# uv-dosimeter-guva-op-amp-mk-1_1.net
KiCad netlist of a schematic drawn in EAGLE
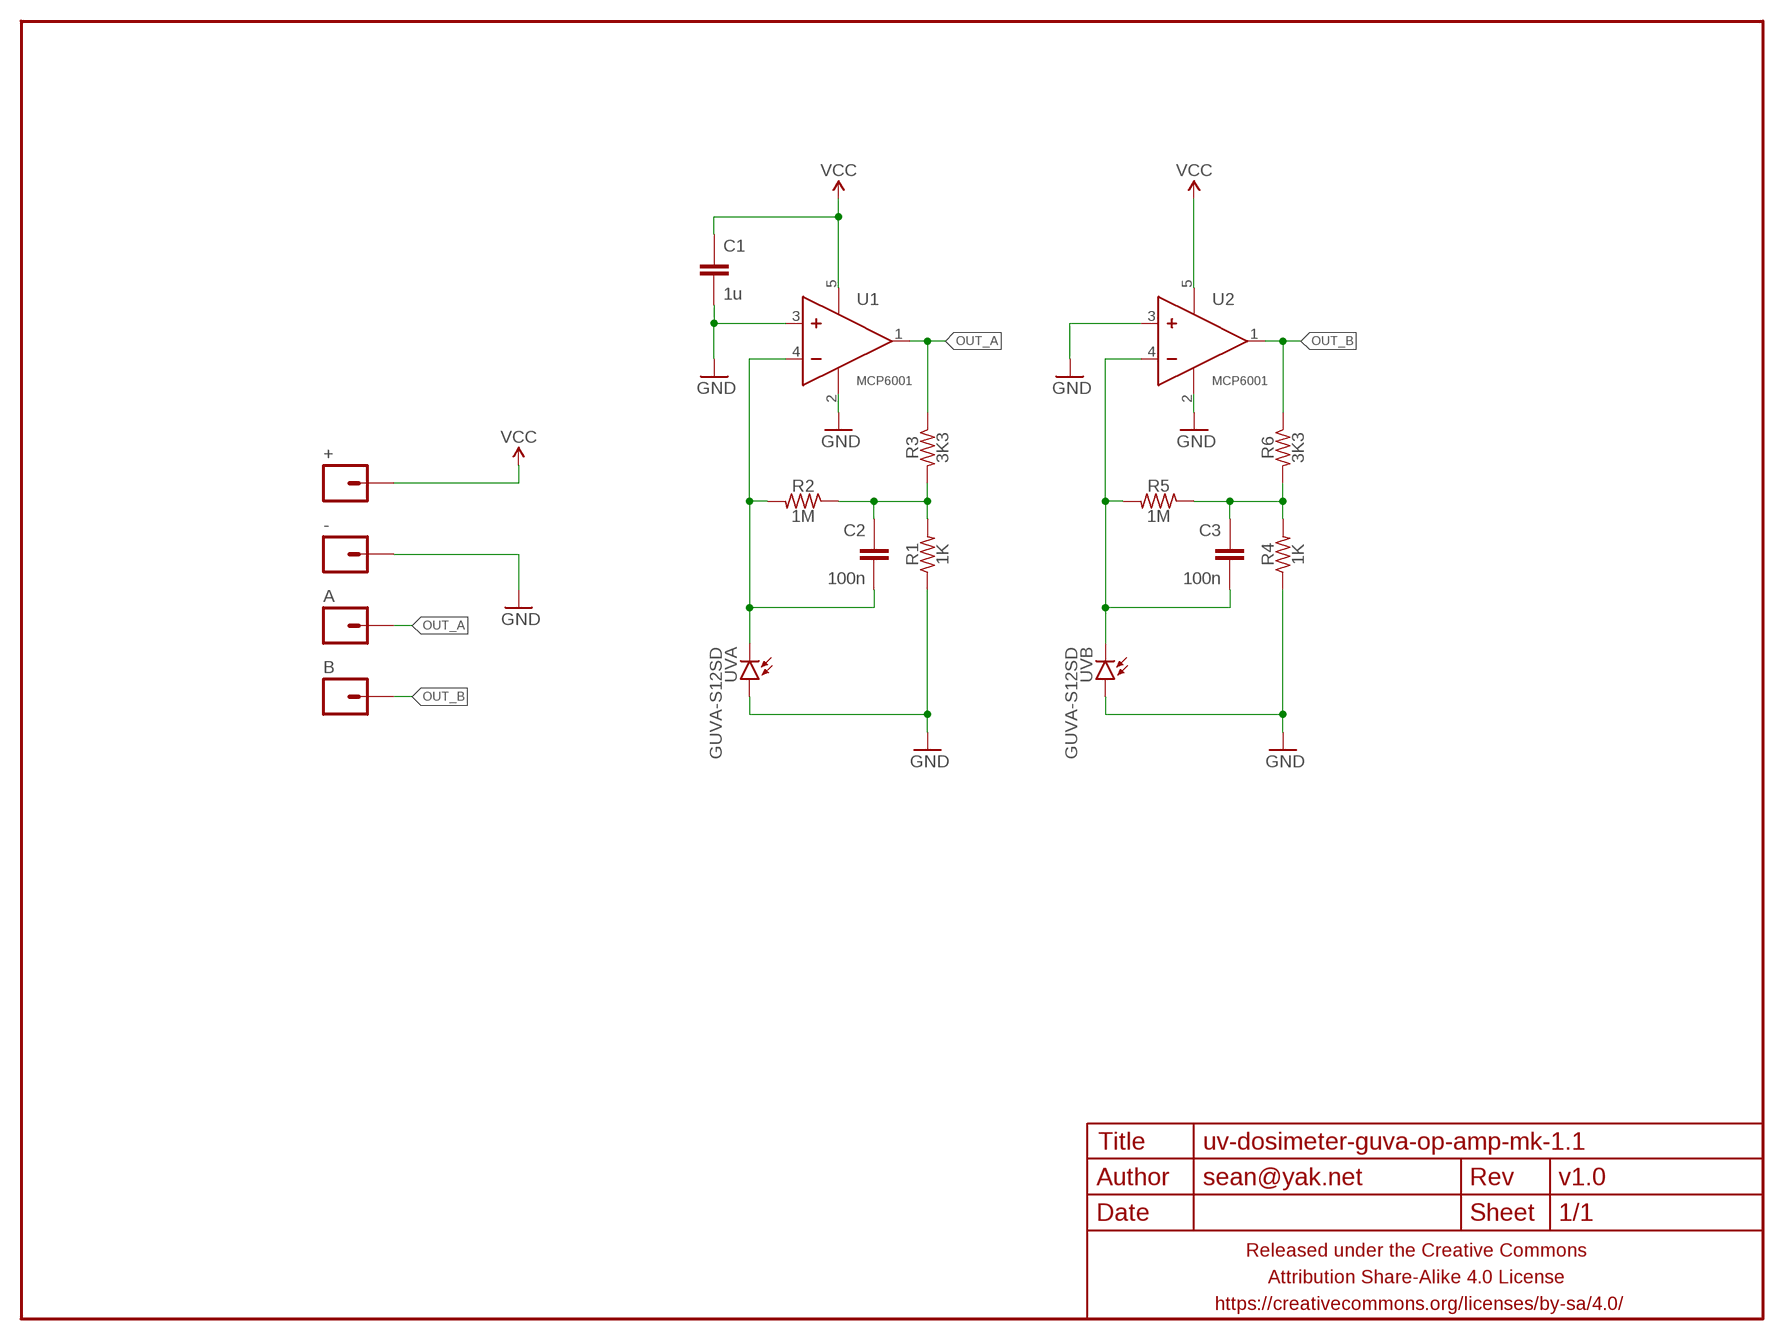
[diagram p0: schematic, sheet 1]

(export (version "E")
  (design (tool "Eeschema 10.0.6"))
  (components
    (comp (ref "+")
      (value "M01PTH")
      (footprint "eagle-import:1X01")
      (libsource (lib "eagle-import") (part "M01PTH"))
    )
    (comp (ref "-")
      (value "M01PTH")
      (footprint "eagle-import:1X01")
      (libsource (lib "eagle-import") (part "M01PTH"))
    )
    (comp (ref "A")
      (value "M01PTH")
      (footprint "eagle-import:1X01")
      (libsource (lib "eagle-import") (part "M01PTH"))
    )
    (comp (ref "B")
      (value "M01PTH")
      (footprint "eagle-import:1X01")
      (libsource (lib "eagle-import") (part "M01PTH"))
    )
    (comp (ref "C1")
      (value "1u")
      (footprint "eagle-import:C0603")
      (libsource (lib "eagle-import") (part "CAPACITOR-CERAMICC0603"))
    )
    (comp (ref "C2")
      (value "100n")
      (footprint "eagle-import:C0603")
      (libsource (lib "eagle-import") (part "CAPACITOR-CERAMICC0603"))
    )
    (comp (ref "C3")
      (value "100n")
      (footprint "eagle-import:C0603")
      (libsource (lib "eagle-import") (part "CAPACITOR-CERAMICC0603"))
    )
    (comp (ref "FRAME1")
      (value "FRAME-LETTERNO_PACKAGE")
      (footprint "eagle-import:DUMMY")
      (fields (field (name "DESIGNER") "sean@yak.net") (field (name "VERSION") "v1.0"))
      (libsource (lib "eagle-import") (part "FRAME-LETTERNO_PACKAGE"))
    )
    (comp (ref "R1")
      (value "1K")
      (footprint "eagle-import:R0603")
      (libsource (lib "eagle-import") (part "RESISTORR0603"))
    )
    (comp (ref "R2")
      (value "1M")
      (footprint "eagle-import:R0603")
      (libsource (lib "eagle-import") (part "RESISTORR0603"))
    )
    (comp (ref "R3")
      (value "3K3")
      (footprint "eagle-import:R0603")
      (libsource (lib "eagle-import") (part "RESISTORR0603"))
    )
    (comp (ref "R4")
      (value "1K")
      (footprint "eagle-import:R0603")
      (libsource (lib "eagle-import") (part "RESISTORR0603"))
    )
    (comp (ref "R5")
      (value "1M")
      (footprint "eagle-import:R0603")
      (libsource (lib "eagle-import") (part "RESISTORR0603"))
    )
    (comp (ref "R6")
      (value "3K3")
      (footprint "eagle-import:R0603")
      (libsource (lib "eagle-import") (part "RESISTORR0603"))
    )
    (comp (ref "U1")
      (value "MCP6001")
      (footprint "eagle-import:SOT23-5")
      (libsource (lib "eagle-import") (part "MCP6001SOT23-5"))
    )
    (comp (ref "U2")
      (value "MCP6001")
      (footprint "eagle-import:SOT23-5")
      (libsource (lib "eagle-import") (part "MCP6001SOT23-5"))
    )
    (comp (ref "UVA")
      (value "GUVA-S12SD")
      (footprint "eagle-import:LED3528")
      (libsource (lib "eagle-import") (part "GUVA-S12SDLED3528"))
    )
    (comp (ref "UVB")
      (value "GUVA-S12SD")
      (footprint "eagle-import:LED3528")
      (libsource (lib "eagle-import") (part "GUVA-S12SDLED3528"))
    )
  )
  (nets
    (net (code "1") (name "GND") (class "Default")
      (node (ref "-") (pin "1") (pinfunction "1_1") (pintype "passive"))
      (node (ref "C1") (pin "2") (pinfunction "2_2") (pintype "passive"))
      (node (ref "R1") (pin "1") (pinfunction "1_1") (pintype "passive"))
      (node (ref "R4") (pin "1") (pinfunction "1_1") (pintype "passive"))
      (node (ref "U1") (pin "2") (pinfunction "V-_2") (pintype "power_in"))
      (node (ref "U1") (pin "3") (pinfunction "IN+_3") (pintype "input"))
      (node (ref "U2") (pin "2") (pinfunction "V-_2") (pintype "power_in"))
      (node (ref "U2") (pin "3") (pinfunction "IN+_3") (pintype "input"))
      (node (ref "UVA") (pin "A") (pinfunction "A_A") (pintype "passive"))
      (node (ref "UVB") (pin "A") (pinfunction "A_A") (pintype "passive"))
    )
    (net (code "2") (name "Net-(C2-Pad1)") (class "Default")
      (node (ref "C2") (pin "1") (pinfunction "1_1") (pintype "passive"))
      (node (ref "R1") (pin "2") (pinfunction "2_2") (pintype "passive"))
      (node (ref "R2") (pin "1") (pinfunction "1_1") (pintype "passive"))
      (node (ref "R3") (pin "2") (pinfunction "2_2") (pintype "passive"))
    )
    (net (code "3") (name "Net-(C3-Pad1)") (class "Default")
      (node (ref "C3") (pin "1") (pinfunction "1_1") (pintype "passive"))
      (node (ref "R4") (pin "2") (pinfunction "2_2") (pintype "passive"))
      (node (ref "R5") (pin "1") (pinfunction "1_1") (pintype "passive"))
      (node (ref "R6") (pin "2") (pinfunction "2_2") (pintype "passive"))
    )
    (net (code "4") (name "Net-(U1-IN-)") (class "Default")
      (node (ref "C2") (pin "2") (pinfunction "2_2") (pintype "passive"))
      (node (ref "R2") (pin "2") (pinfunction "2_2") (pintype "passive"))
      (node (ref "U1") (pin "4") (pinfunction "IN-_4") (pintype "input"))
      (node (ref "UVA") (pin "K") (pinfunction "C_K") (pintype "passive"))
    )
    (net (code "5") (name "Net-(U2-IN-)") (class "Default")
      (node (ref "C3") (pin "2") (pinfunction "2_2") (pintype "passive"))
      (node (ref "R5") (pin "2") (pinfunction "2_2") (pintype "passive"))
      (node (ref "U2") (pin "4") (pinfunction "IN-_4") (pintype "input"))
      (node (ref "UVB") (pin "K") (pinfunction "C_K") (pintype "passive"))
    )
    (net (code "6") (name "OUT_A") (class "Default")
      (node (ref "A") (pin "1") (pinfunction "1_1") (pintype "passive"))
      (node (ref "R3") (pin "1") (pinfunction "1_1") (pintype "passive"))
      (node (ref "U1") (pin "1") (pinfunction "OUT_1") (pintype "output"))
    )
    (net (code "7") (name "OUT_B") (class "Default")
      (node (ref "B") (pin "1") (pinfunction "1_1") (pintype "passive"))
      (node (ref "R6") (pin "1") (pinfunction "1_1") (pintype "passive"))
      (node (ref "U2") (pin "1") (pinfunction "OUT_1") (pintype "output"))
    )
    (net (code "8") (name "VCC") (class "Default")
      (node (ref "+") (pin "1") (pinfunction "1_1") (pintype "passive"))
      (node (ref "C1") (pin "1") (pinfunction "1_1") (pintype "passive"))
      (node (ref "U1") (pin "5") (pinfunction "V+_5") (pintype "power_in"))
      (node (ref "U2") (pin "5") (pinfunction "V+_5") (pintype "power_in"))
    )
  )
)
